# Current_Sensor.net
KiCad netlist of a schematic drawn in Altium Designer
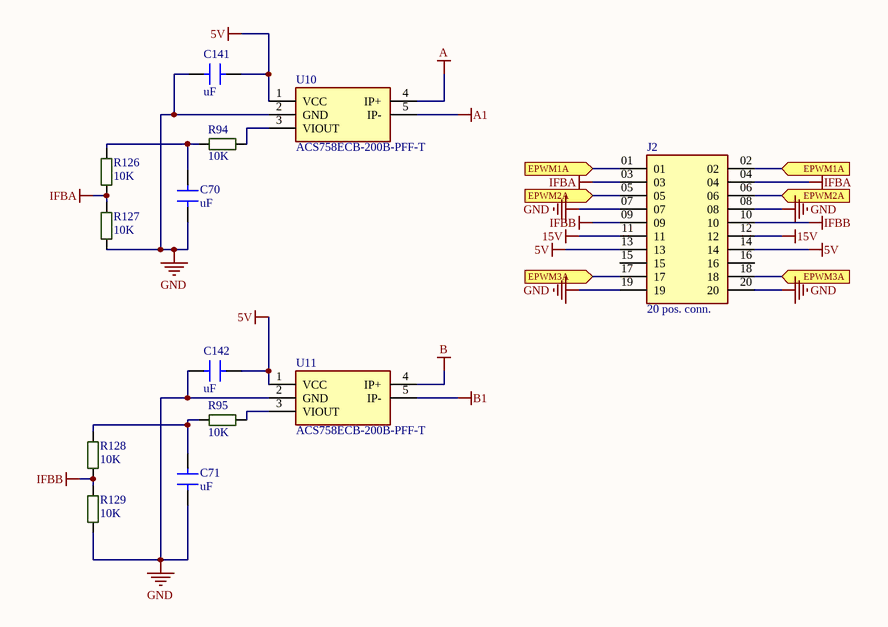
[diagram p0: Current_Sensor.SchDoc]

(export (version "E")
  (design (tool "Eeschema 10.0.6"))
  (components
    (comp (ref "C70") (value "uF") (footprint "C-1206") (libsource (lib "PROJE") (part "C-1206")))
    (comp (ref "C71") (value "uF") (footprint "C-1206") (libsource (lib "PROJE") (part "C-1206")))
    (comp (ref "C141") (value "uF") (footprint "C-1206") (libsource (lib "PROJE") (part "C-1206")))
    (comp (ref "C142") (value "uF") (footprint "C-1206") (libsource (lib "PROJE") (part "C-1206")))
    (comp (ref "J2")
      (value "20 pos. conn.")
      (footprint "SAMTEC_SSQ-110-X-X-D")
      (description "SSQ - Samtec 2.54mm Square Tail Dual Row Socket Strip 8.5mm Profile - Fast Stock")
      (fields (field (name "MF") "Samtec") (field (name "MP") "SSQ-110-23-G-D"))
      (libsource (lib "PROJE") (part "20 pos. conn."))
    )
    (comp (ref "R94")
      (value "10K")
      (footprint "R-1206")
      (description "1206S4F1002T5E")
      (libsource (lib "PROJE") (part "R-1206_GS"))
    )
    (comp (ref "R95")
      (value "10K")
      (footprint "R-1206")
      (description "1206S4F1002T5E")
      (libsource (lib "PROJE") (part "R-1206_GS"))
    )
    (comp (ref "R126")
      (value "10K")
      (footprint "R-1206")
      (description "1206S4F1002T5E")
      (libsource (lib "PROJE") (part "R-1206_GS"))
    )
    (comp (ref "R127")
      (value "10K")
      (footprint "R-1206")
      (description "1206S4F1002T5E")
      (libsource (lib "PROJE") (part "R-1206_GS"))
    )
    (comp (ref "R128")
      (value "10K")
      (footprint "R-1206")
      (description "1206S4F1002T5E")
      (libsource (lib "PROJE") (part "R-1206_GS"))
    )
    (comp (ref "R129")
      (value "10K")
      (footprint "R-1206")
      (description "1206S4F1002T5E")
      (libsource (lib "PROJE") (part "R-1206_GS"))
    )
    (comp (ref "U10")
      (value "ACS758ECB-200B-PFF-T")
      (footprint "ACS756SCA-050B-PFF-T_2")
      (description "Undefined or Miscellaneous")
      (libsource (lib "PROJE") (part "ACS758ECB-200B-PFF-T"))
    )
    (comp (ref "U11")
      (value "ACS758ECB-200B-PFF-T")
      (footprint "ACS756SCA-050B-PFF-T_2")
      (description "Undefined or Miscellaneous")
      (libsource (lib "PROJE") (part "ACS758ECB-200B-PFF-T"))
    )
  )
  (nets
    (net (code "1") (name "/EPWM1A") (class "Default")
      (node (ref "J2") (pin "01") (pinfunction "01_01") (pintype "passive"))
      (node (ref "J2") (pin "02") (pinfunction "02_02") (pintype "passive"))
    )
    (net (code "2") (name "/EPWM2A") (class "Default")
      (node (ref "J2") (pin "05") (pinfunction "05_05") (pintype "passive"))
      (node (ref "J2") (pin "06") (pinfunction "06_06") (pintype "passive"))
    )
    (net (code "3") (name "/EPWM3A") (class "Default")
      (node (ref "J2") (pin "17") (pinfunction "17_17") (pintype "passive"))
      (node (ref "J2") (pin "18") (pinfunction "18_18") (pintype "passive"))
    )
    (net (code "4") (name "5V") (class "Default")
      (node (ref "C141") (pin "1") (pinfunction "1_1") (pintype "passive"))
      (node (ref "C142") (pin "1") (pinfunction "1_1") (pintype "passive"))
      (node (ref "J2") (pin "13") (pinfunction "13_13") (pintype "passive"))
      (node (ref "J2") (pin "14") (pinfunction "14_14") (pintype "passive"))
      (node (ref "U10") (pin "1") (pinfunction "VCC_1") (pintype "passive"))
      (node (ref "U11") (pin "1") (pinfunction "VCC_1") (pintype "passive"))
    )
    (net (code "5") (name "15V") (class "Default")
      (node (ref "J2") (pin "11") (pinfunction "11_11") (pintype "passive"))
      (node (ref "J2") (pin "12") (pinfunction "12_12") (pintype "passive"))
    )
    (net (code "6") (name "A") (class "Default")
      (node (ref "U10") (pin "4") (pinfunction "IP+_4") (pintype "passive"))
    )
    (net (code "7") (name "A1") (class "Default")
      (node (ref "U10") (pin "5") (pinfunction "IP-_5") (pintype "passive"))
    )
    (net (code "8") (name "B") (class "Default")
      (node (ref "U11") (pin "4") (pinfunction "IP+_4") (pintype "passive"))
    )
    (net (code "9") (name "B1") (class "Default")
      (node (ref "U11") (pin "5") (pinfunction "IP-_5") (pintype "passive"))
    )
    (net (code "10") (name "GND") (class "Default")
      (node (ref "C141") (pin "2") (pinfunction "2_2") (pintype "passive"))
      (node (ref "C142") (pin "2") (pinfunction "2_2") (pintype "passive"))
      (node (ref "C70") (pin "1") (pinfunction "1_1") (pintype "passive"))
      (node (ref "C71") (pin "1") (pinfunction "1_1") (pintype "passive"))
      (node (ref "J2") (pin "07") (pinfunction "07_07") (pintype "passive"))
      (node (ref "J2") (pin "08") (pinfunction "08_08") (pintype "passive"))
      (node (ref "J2") (pin "19") (pinfunction "19_19") (pintype "passive"))
      (node (ref "J2") (pin "20") (pinfunction "20_20") (pintype "passive"))
      (node (ref "R127") (pin "2") (pinfunction "2_2") (pintype "passive"))
      (node (ref "R129") (pin "2") (pinfunction "2_2") (pintype "passive"))
      (node (ref "U10") (pin "2") (pinfunction "GND_2") (pintype "passive"))
      (node (ref "U11") (pin "2") (pinfunction "GND_2") (pintype "passive"))
    )
    (net (code "11") (name "IFBA") (class "Default")
      (node (ref "J2") (pin "03") (pinfunction "03_03") (pintype "passive"))
      (node (ref "J2") (pin "04") (pinfunction "04_04") (pintype "passive"))
      (node (ref "R126") (pin "2") (pinfunction "2_2") (pintype "passive"))
      (node (ref "R127") (pin "1") (pinfunction "1_1") (pintype "passive"))
    )
    (net (code "12") (name "IFBB") (class "Default")
      (node (ref "J2") (pin "09") (pinfunction "09_09") (pintype "passive"))
      (node (ref "J2") (pin "10") (pinfunction "10_10") (pintype "passive"))
      (node (ref "R128") (pin "2") (pinfunction "2_2") (pintype "passive"))
      (node (ref "R129") (pin "1") (pinfunction "1_1") (pintype "passive"))
    )
    (net (code "13") (name "Net-(C70-Pad2)") (class "Default")
      (node (ref "C70") (pin "2") (pinfunction "2_2") (pintype "passive"))
      (node (ref "R126") (pin "1") (pinfunction "1_1") (pintype "passive"))
      (node (ref "R94") (pin "2") (pinfunction "2_2") (pintype "passive"))
    )
    (net (code "14") (name "Net-(C71-Pad2)") (class "Default")
      (node (ref "C71") (pin "2") (pinfunction "2_2") (pintype "passive"))
      (node (ref "R128") (pin "1") (pinfunction "1_1") (pintype "passive"))
      (node (ref "R95") (pin "2") (pinfunction "2_2") (pintype "passive"))
    )
    (net (code "15") (name "Net-(U10-VIOUT)") (class "Default")
      (node (ref "R94") (pin "1") (pinfunction "1_1") (pintype "passive"))
      (node (ref "U10") (pin "3") (pinfunction "VIOUT_3") (pintype "passive"))
    )
    (net (code "16") (name "Net-(U11-VIOUT)") (class "Default")
      (node (ref "R95") (pin "1") (pinfunction "1_1") (pintype "passive"))
      (node (ref "U11") (pin "3") (pinfunction "VIOUT_3") (pintype "passive"))
    )
    (net (code "17") (name "unconnected-(J2-Pad15)") (class "Default")
      (node (ref "J2") (pin "15") (pinfunction "15_15") (pintype "passive"))
    )
    (net (code "18") (name "unconnected-(J2-Pad16)") (class "Default")
      (node (ref "J2") (pin "16") (pinfunction "16_16") (pintype "passive"))
    )
  )
)
